# Circuit.net
KiCad netlist of a schematic drawn in EAGLE
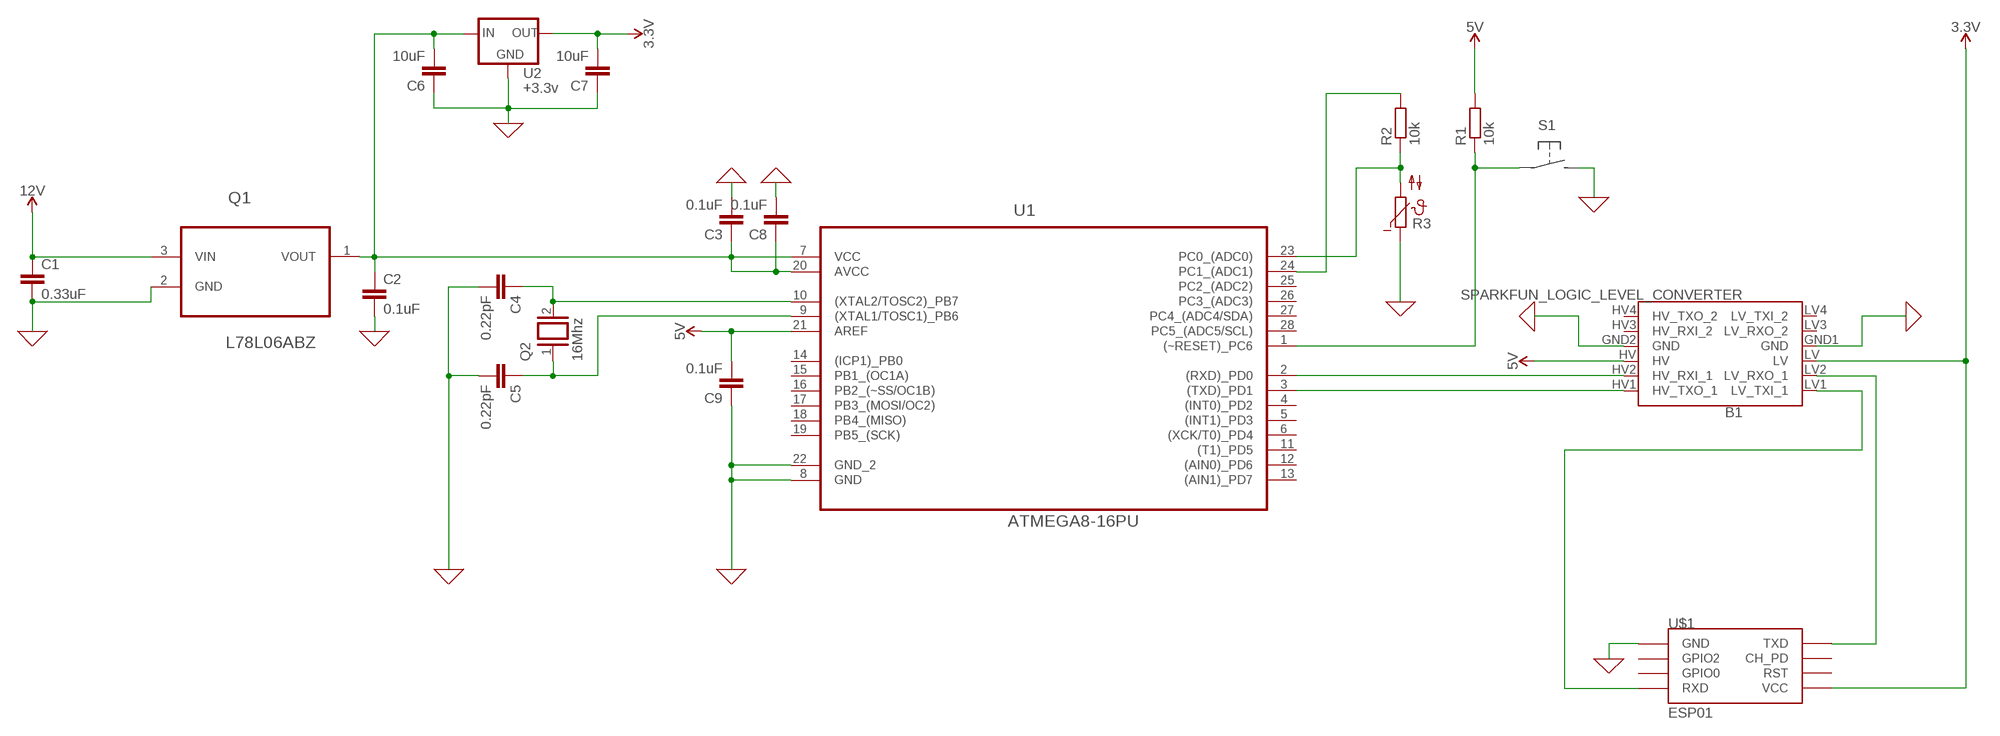
[diagram p0: schematic, sheet 1]

(export (version "E")
  (design (tool "Eeschema 10.0.6"))
  (components
    (comp (ref "B1")
      (value "SPARKFUN_LOGIC_LEVEL_CONVERTER")
      (footprint "eagle-import:SPARKFUN_LOGIC_LEVEL_CONVERTER")
      (libsource (lib "eagle-import") (part "SPARKFUN_LOGIC_LEVEL_CONVERTER"))
    )
    (comp (ref "C1")
      (value "0.33uF")
      (footprint "eagle-import:C050-025X075")
      (libsource (lib "eagle-import") (part "C-EU050-025X075"))
    )
    (comp (ref "C2")
      (value "0.1uF")
      (footprint "eagle-import:C050-025X075")
      (libsource (lib "eagle-import") (part "C-EU050-025X075"))
    )
    (comp (ref "C3")
      (value "0.1uF")
      (footprint "eagle-import:C050-025X075")
      (libsource (lib "eagle-import") (part "C-EU050-025X075"))
    )
    (comp (ref "C4")
      (value "0.22pF")
      (footprint "eagle-import:C050-025X075")
      (libsource (lib "eagle-import") (part "C-EU050-025X075"))
    )
    (comp (ref "C5")
      (value "0.22pF")
      (footprint "eagle-import:C050-025X075")
      (libsource (lib "eagle-import") (part "C-EU050-025X075"))
    )
    (comp (ref "C6")
      (value "10uF")
      (footprint "eagle-import:C050-025X075")
      (libsource (lib "eagle-import") (part "C-EU050-025X075"))
    )
    (comp (ref "C7")
      (value "10uF")
      (footprint "eagle-import:C050-025X075")
      (libsource (lib "eagle-import") (part "C-EU050-025X075"))
    )
    (comp (ref "C8")
      (value "0.1uF")
      (footprint "eagle-import:C050-025X075")
      (libsource (lib "eagle-import") (part "C-EU050-025X075"))
    )
    (comp (ref "C9")
      (value "0.1uF")
      (footprint "eagle-import:C050-025X075")
      (libsource (lib "eagle-import") (part "C-EU050-025X075"))
    )
    (comp (ref "Q1")
      (value "L78L06ABZ")
      (footprint "eagle-import:TO127P254X749-3")
      (libsource (lib "eagle-import") (part "L78L06ABZ"))
    )
    (comp (ref "Q2")
      (value "16Mhz")
      (footprint "eagle-import:Q")
      (libsource (lib "eagle-import") (part "XTAL"))
    )
    (comp (ref "R1")
      (value "10k")
      (footprint "eagle-import:VTA56")
      (libsource (lib "eagle-import") (part "R-EU_VTA56"))
    )
    (comp (ref "R2")
      (value "10k")
      (footprint "eagle-import:VTA56")
      (libsource (lib "eagle-import") (part "R-EU_VTA56"))
    )
    (comp (ref "R3")
      (value "NTC640")
      (footprint "eagle-import:P640")
      (libsource (lib "eagle-import") (part "NTC640"))
    )
    (comp (ref "U$1")
      (value "ESP01")
      (footprint "eagle-import:ESP01")
      (libsource (lib "eagle-import") (part "ESP01"))
    )
    (comp (ref "U1")
      (value "ATMEGA8-16PU")
      (footprint "eagle-import:DIP254P762X457-28")
      (libsource (lib "eagle-import") (part "ATMEGA8-16PU"))
    )
    (comp (ref "U2")
      (value "+3.3v")
      (footprint "eagle-import:TO-252")
      (libsource (lib "eagle-import") (part "V_REG_78XX7812"))
    )
  )
  (nets
    (net (code "1") (name "3.3V") (class "Default")
      (node (ref "B1") (pin "LV") (pinfunction "LV_LV") (pintype "power_in"))
      (node (ref "C7") (pin "2") (pinfunction "2_2") (pintype "passive"))
      (node (ref "U$1") (pin "VCC") (pinfunction "VCC_VCC") (pintype "bidirectional"))
      (node (ref "U2") (pin "2") (pinfunction "OUT_2") (pintype "passive"))
    )
    (net (code "2") (name "5V") (class "Default")
      (node (ref "B1") (pin "HV") (pinfunction "HV_HV") (pintype "power_in"))
      (node (ref "C9") (pin "2") (pinfunction "2_2") (pintype "passive"))
      (node (ref "R1") (pin "2") (pinfunction "2_2") (pintype "passive"))
      (node (ref "U1") (pin "21") (pinfunction "AREF_21") (pintype "input"))
    )
    (net (code "3") (name "12V") (class "Default")
      (node (ref "C1") (pin "1") (pinfunction "1_1") (pintype "passive"))
      (node (ref "Q1") (pin "3") (pinfunction "VIN_3") (pintype "power_in"))
    )
    (net (code "4") (name "GND") (class "Default")
      (node (ref "B1") (pin "GND1") (pinfunction "GND_GND1") (pintype "power_in"))
      (node (ref "B1") (pin "GND2") (pinfunction "GND_GND2") (pintype "power_in"))
      (node (ref "C1") (pin "2") (pinfunction "2_2") (pintype "passive"))
      (node (ref "C2") (pin "2") (pinfunction "2_2") (pintype "passive"))
      (node (ref "C3") (pin "2") (pinfunction "2_2") (pintype "passive"))
      (node (ref "C4") (pin "2") (pinfunction "2_2") (pintype "passive"))
      (node (ref "C5") (pin "2") (pinfunction "2_2") (pintype "passive"))
      (node (ref "C6") (pin "1") (pinfunction "1_1") (pintype "passive"))
      (node (ref "C7") (pin "1") (pinfunction "1_1") (pintype "passive"))
      (node (ref "C8") (pin "2") (pinfunction "2_2") (pintype "passive"))
      (node (ref "C9") (pin "1") (pinfunction "1_1") (pintype "passive"))
      (node (ref "Q1") (pin "2") (pinfunction "GND_2") (pintype "passive"))
      (node (ref "R3") (pin "1") (pinfunction "1_1") (pintype "passive"))
      (node (ref "U$1") (pin "GND") (pinfunction "GND_GND") (pintype "bidirectional"))
      (node (ref "U1") (pin "22") (pinfunction "GND_2_22") (pintype "passive"))
      (node (ref "U1") (pin "8") (pinfunction "GND_8") (pintype "passive"))
      (node (ref "U2") (pin "3") (pinfunction "GND_3") (pintype "input"))
    )
    (net (code "5") (name "Net-(B1-HV_RXI_1)") (class "Default")
      (node (ref "B1") (pin "HV2") (pinfunction "HV_RXI_1_HV2") (pintype "bidirectional"))
      (node (ref "U1") (pin "2") (pinfunction "(RXD)_PD0_2") (pintype "bidirectional"))
    )
    (net (code "6") (name "Net-(B1-HV_TXO_1)") (class "Default")
      (node (ref "B1") (pin "HV1") (pinfunction "HV_TXO_1_HV1") (pintype "bidirectional"))
      (node (ref "U1") (pin "3") (pinfunction "(TXD)_PD1_3") (pintype "bidirectional"))
    )
    (net (code "7") (name "Net-(B1-LV_RXO_1)") (class "Default")
      (node (ref "B1") (pin "LV2") (pinfunction "LV_RXO_1_LV2") (pintype "bidirectional"))
      (node (ref "U$1") (pin "TX") (pinfunction "TXD_TX") (pintype "bidirectional"))
    )
    (net (code "8") (name "Net-(B1-LV_TXI_1)") (class "Default")
      (node (ref "B1") (pin "LV1") (pinfunction "LV_TXI_1_LV1") (pintype "bidirectional"))
      (node (ref "U$1") (pin "RX") (pinfunction "RXD_RX") (pintype "bidirectional"))
    )
    (net (code "9") (name "Net-(Q1-VOUT)") (class "Default")
      (node (ref "C2") (pin "1") (pinfunction "1_1") (pintype "passive"))
      (node (ref "C3") (pin "1") (pinfunction "1_1") (pintype "passive"))
      (node (ref "C6") (pin "2") (pinfunction "2_2") (pintype "passive"))
      (node (ref "C8") (pin "1") (pinfunction "1_1") (pintype "passive"))
      (node (ref "Q1") (pin "1") (pinfunction "VOUT_1") (pintype "output"))
      (node (ref "U1") (pin "20") (pinfunction "AVCC_20") (pintype "power_in"))
      (node (ref "U1") (pin "7") (pinfunction "VCC_7") (pintype "power_in"))
      (node (ref "U2") (pin "1") (pinfunction "IN_1") (pintype "input"))
    )
    (net (code "10") (name "Net-(U1-(XTAL1{slash}TOSC1)_PB6)") (class "Default")
      (node (ref "C5") (pin "1") (pinfunction "1_1") (pintype "passive"))
      (node (ref "Q2") (pin "1") (pinfunction "1_1") (pintype "passive"))
      (node (ref "U1") (pin "9") (pinfunction "(XTAL1/TOSC1)_PB6_9") (pintype "input"))
    )
    (net (code "11") (name "Net-(U1-(XTAL2{slash}TOSC2)_PB7)") (class "Default")
      (node (ref "C4") (pin "1") (pinfunction "1_1") (pintype "passive"))
      (node (ref "Q2") (pin "2") (pinfunction "2_2") (pintype "passive"))
      (node (ref "U1") (pin "10") (pinfunction "(XTAL2/TOSC2)_PB7_10") (pintype "input"))
    )
    (net (code "12") (name "Net-(U1-(~{RESET})_PC6)") (class "Default")
      (node (ref "R1") (pin "1") (pinfunction "1_1") (pintype "passive"))
      (node (ref "U1") (pin "1") (pinfunction "(~{RESET})_PC6_1") (pintype "bidirectional"))
    )
    (net (code "13") (name "Net-(U1-PC0_(ADC0))") (class "Default")
      (node (ref "R2") (pin "1") (pinfunction "1_1") (pintype "passive"))
      (node (ref "R3") (pin "2") (pinfunction "2_2") (pintype "passive"))
      (node (ref "U1") (pin "23") (pinfunction "PC0_(ADC0)_23") (pintype "bidirectional"))
    )
    (net (code "14") (name "Net-(U1-PC1_(ADC1))") (class "Default")
      (node (ref "R2") (pin "2") (pinfunction "2_2") (pintype "passive"))
      (node (ref "U1") (pin "24") (pinfunction "PC1_(ADC1)_24") (pintype "bidirectional"))
    )
    (net (code "15") (name "unconnected-(B1-HV_RXI_2-PadHV3)") (class "Default")
      (node (ref "B1") (pin "HV3") (pinfunction "HV_RXI_2_HV3") (pintype "bidirectional"))
    )
    (net (code "16") (name "unconnected-(B1-HV_TXO_2-PadHV4)") (class "Default")
      (node (ref "B1") (pin "HV4") (pinfunction "HV_TXO_2_HV4") (pintype "bidirectional"))
    )
    (net (code "17") (name "unconnected-(B1-LV_RXO_2-PadLV3)") (class "Default")
      (node (ref "B1") (pin "LV3") (pinfunction "LV_RXO_2_LV3") (pintype "bidirectional"))
    )
    (net (code "18") (name "unconnected-(B1-LV_TXI_2-PadLV4)") (class "Default")
      (node (ref "B1") (pin "LV4") (pinfunction "LV_TXI_2_LV4") (pintype "bidirectional"))
    )
    (net (code "19") (name "unconnected-(U$1-PadCH_PD)") (class "Default")
      (node (ref "U$1") (pin "CH_PD") (pinfunction "CH_PD_CH_PD") (pintype "bidirectional"))
    )
    (net (code "20") (name "unconnected-(U$1-PadGPIO0)") (class "Default")
      (node (ref "U$1") (pin "GPIO0") (pinfunction "GPIO0_GPIO0") (pintype "bidirectional"))
    )
    (net (code "21") (name "unconnected-(U$1-PadGPIO2)") (class "Default")
      (node (ref "U$1") (pin "GPIO2") (pinfunction "GPIO2_GPIO2") (pintype "bidirectional"))
    )
    (net (code "22") (name "unconnected-(U$1-PadRST)") (class "Default")
      (node (ref "U$1") (pin "RST") (pinfunction "RST_RST") (pintype "bidirectional"))
    )
    (net (code "23") (name "unconnected-(U1-(AIN0)_PD6-Pad12)") (class "Default")
      (node (ref "U1") (pin "12") (pinfunction "(AIN0)_PD6_12") (pintype "bidirectional"))
    )
    (net (code "24") (name "unconnected-(U1-(AIN1)_PD7-Pad13)") (class "Default")
      (node (ref "U1") (pin "13") (pinfunction "(AIN1)_PD7_13") (pintype "bidirectional"))
    )
    (net (code "25") (name "unconnected-(U1-(ICP1)_PB0-Pad14)") (class "Default")
      (node (ref "U1") (pin "14") (pinfunction "(ICP1)_PB0_14") (pintype "bidirectional"))
    )
    (net (code "26") (name "unconnected-(U1-(INT0)_PD2-Pad4)") (class "Default")
      (node (ref "U1") (pin "4") (pinfunction "(INT0)_PD2_4") (pintype "bidirectional"))
    )
    (net (code "27") (name "unconnected-(U1-(INT1)_PD3-Pad5)") (class "Default")
      (node (ref "U1") (pin "5") (pinfunction "(INT1)_PD3_5") (pintype "bidirectional"))
    )
    (net (code "28") (name "unconnected-(U1-(T1)_PD5-Pad11)") (class "Default")
      (node (ref "U1") (pin "11") (pinfunction "(T1)_PD5_11") (pintype "bidirectional"))
    )
    (net (code "29") (name "unconnected-(U1-(XCK{slash}T0)_PD4-Pad6)") (class "Default")
      (node (ref "U1") (pin "6") (pinfunction "(XCK/T0)_PD4_6") (pintype "bidirectional"))
    )
    (net (code "30") (name "unconnected-(U1-PB1_(OC1A)-Pad15)") (class "Default")
      (node (ref "U1") (pin "15") (pinfunction "PB1_(OC1A)_15") (pintype "bidirectional"))
    )
    (net (code "31") (name "unconnected-(U1-PB2_(~{SS{slash}OC1B})-Pad16)") (class "Default")
      (node (ref "U1") (pin "16") (pinfunction "PB2_(~{SS/OC1B})_16") (pintype "bidirectional"))
    )
    (net (code "32") (name "unconnected-(U1-PB3_(MOSI{slash}OC2)-Pad17)") (class "Default")
      (node (ref "U1") (pin "17") (pinfunction "PB3_(MOSI/OC2)_17") (pintype "bidirectional"))
    )
    (net (code "33") (name "unconnected-(U1-PB4_(MISO)-Pad18)") (class "Default")
      (node (ref "U1") (pin "18") (pinfunction "PB4_(MISO)_18") (pintype "bidirectional"))
    )
    (net (code "34") (name "unconnected-(U1-PB5_(SCK)-Pad19)") (class "Default")
      (node (ref "U1") (pin "19") (pinfunction "PB5_(SCK)_19") (pintype "bidirectional"))
    )
    (net (code "35") (name "unconnected-(U1-PC2_(ADC2)-Pad25)") (class "Default")
      (node (ref "U1") (pin "25") (pinfunction "PC2_(ADC2)_25") (pintype "bidirectional"))
    )
    (net (code "36") (name "unconnected-(U1-PC3_(ADC3)-Pad26)") (class "Default")
      (node (ref "U1") (pin "26") (pinfunction "PC3_(ADC3)_26") (pintype "bidirectional"))
    )
    (net (code "37") (name "unconnected-(U1-PC4_(ADC4{slash}SDA)-Pad27)") (class "Default")
      (node (ref "U1") (pin "27") (pinfunction "PC4_(ADC4/SDA)_27") (pintype "bidirectional"))
    )
    (net (code "38") (name "unconnected-(U1-PC5_(ADC5{slash}SCL)-Pad28)") (class "Default")
      (node (ref "U1") (pin "28") (pinfunction "PC5_(ADC5/SCL)_28") (pintype "bidirectional"))
    )
  )
)
